# LB_BIT_i3_BUTTON-v02_rev1.net
KiCad netlist of a schematic drawn in EAGLE
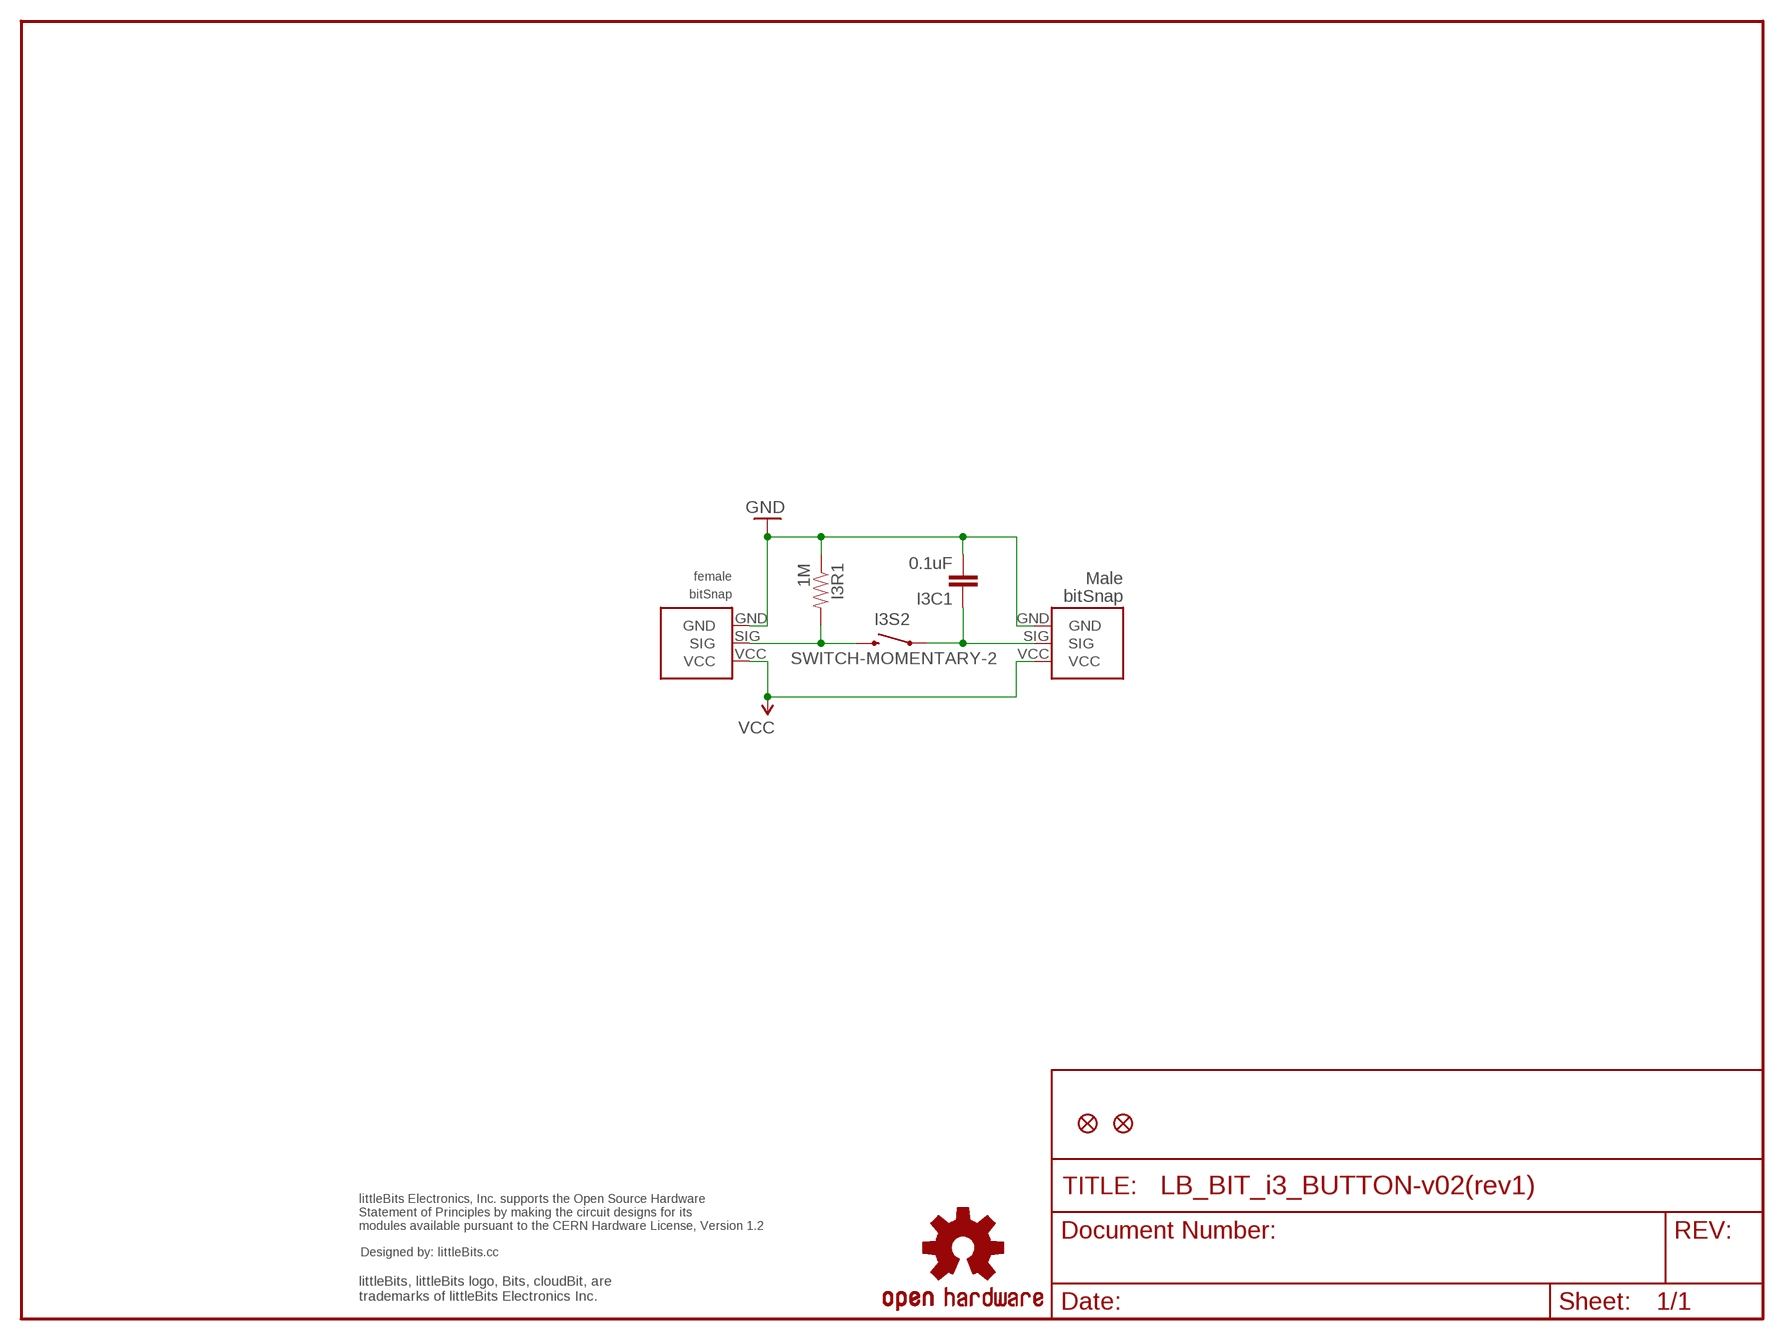
[diagram p0: schematic, sheet 1]

(export (version "E")
  (design (tool "Eeschema 10.0.6"))
  (components
    (comp (ref "I3BSF")
      (value "BITSNAP_FEMALE")
      (footprint "eagle-import:BITSNAP_FEMALE")
      (libsource (lib "eagle-import") (part "BITSNAP_FEMALE"))
    )
    (comp (ref "I3BSM")
      (value "BITSNAP_MALE")
      (footprint "eagle-import:BITSNAP_MALE")
      (libsource (lib "eagle-import") (part "BITSNAP_MALE"))
    )
    (comp (ref "I3C1")
      (value "0.1uF")
      (footprint "eagle-import:0603-CAP")
      (libsource (lib "eagle-import") (part "CAP0603-CAP"))
    )
    (comp (ref "I3R1")
      (value "1M")
      (footprint "eagle-import:0603-RES")
      (libsource (lib "eagle-import") (part "RESISTOR0603-RES"))
    )
    (comp (ref "I3S2")
      (value "SWITCH-MOMENTARY-2")
      (footprint "eagle-import:TACTILE_SWITCH_TALL")
      (libsource (lib "eagle-import") (part "SWITCH-MOMENTARY-2"))
    )
    (comp (ref "JP1")
      (value "FIDUCIAL1X2.5")
      (footprint "eagle-import:FIDUCIAL-1X2.5")
      (libsource (lib "eagle-import") (part "FIDUCIAL1X2.5"))
    )
    (comp (ref "JP2")
      (value "FIDUCIAL1X2.5")
      (footprint "eagle-import:FIDUCIAL-1X2.5")
      (libsource (lib "eagle-import") (part "FIDUCIAL1X2.5"))
    )
    (comp (ref "U$1")
      (value "OSHW-LOGOL")
      (footprint "eagle-import:OSHW-LOGO-L")
      (libsource (lib "eagle-import") (part "OSHW-LOGOL"))
    )
    (comp (ref "U$2")
      (value "OSHWCREDIT")
      (footprint "eagle-import:OSHWCREDIT")
      (libsource (lib "eagle-import") (part "OSHWCREDIT"))
    )
  )
  (nets
    (net (code "1") (name "GND") (class "Default")
      (node (ref "I3BSF") (pin "GND") (pinfunction "GND_GND") (pintype "bidirectional"))
      (node (ref "I3BSM") (pin "GND") (pinfunction "GND_GND") (pintype "bidirectional"))
      (node (ref "I3C1") (pin "2") (pinfunction "2_2") (pintype "passive"))
      (node (ref "I3R1") (pin "1") (pinfunction "1_1") (pintype "passive"))
    )
    (net (code "2") (name "Net-(I3S2-1)") (class "Default")
      (node (ref "I3BSM") (pin "SIG") (pinfunction "SIG_SIG") (pintype "bidirectional"))
      (node (ref "I3C1") (pin "1") (pinfunction "1_1") (pintype "passive"))
      (node (ref "I3S2") (pin "A2") (pinfunction "1_A2") (pintype "passive"))
    )
    (net (code "3") (name "Net-(I3S2-2)") (class "Default")
      (node (ref "I3BSF") (pin "SIG") (pinfunction "SIG_SIG") (pintype "bidirectional"))
      (node (ref "I3R1") (pin "2") (pinfunction "2_2") (pintype "passive"))
      (node (ref "I3S2") (pin "B2") (pinfunction "2_B2") (pintype "passive"))
    )
    (net (code "4") (name "VCC") (class "Default")
      (node (ref "I3BSF") (pin "VCC") (pinfunction "VCC_VCC") (pintype "bidirectional"))
      (node (ref "I3BSM") (pin "VCC") (pinfunction "VCC_VCC") (pintype "bidirectional"))
    )
  )
)
